# RPiHeatingArduinoOilSensorTCP.net
KiCad netlist of a schematic drawn in EAGLE
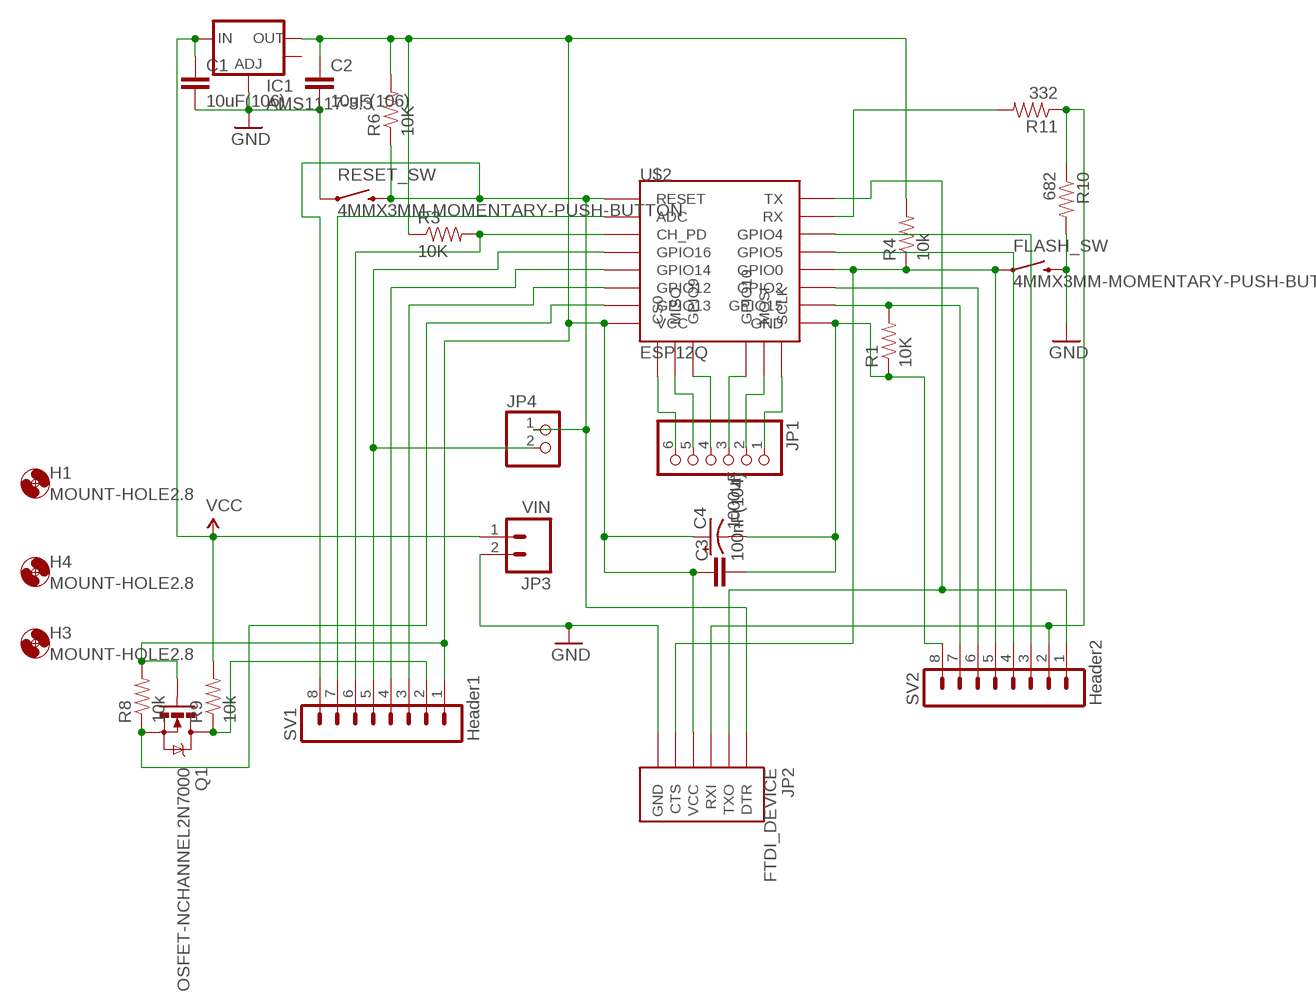
[diagram p0: schematic, sheet 1]

(export (version "E")
  (design (tool "Eeschema 10.0.6"))
  (components
    (comp (ref "C1")
      (value "10uF(106)")
      (footprint "eagle-import:0805")
      (libsource (lib "eagle-import") (part "CAP0805"))
    )
    (comp (ref "C2")
      (value "10uF(106)")
      (footprint "eagle-import:0805")
      (libsource (lib "eagle-import") (part "CAP0805"))
    )
    (comp (ref "C3")
      (value "100nF(104)")
      (footprint "eagle-import:0805")
      (libsource (lib "eagle-import") (part "CAP0805"))
    )
    (comp (ref "C4")
      (value "1000uF")
      (footprint "eagle-import:CPOL-RADIAL-1000UF-25V")
      (libsource (lib "eagle-import") (part "CAP_POLPTH4"))
    )
    (comp (ref "FLASH_SW")
      (value "4MMX3MM-MOMENTARY-PUSH-BUTTON")
      (footprint "eagle-import:4MMX3MM-MOMENTARY-PUSH-BUTTON")
      (libsource (lib "eagle-import") (part "4MMX3MM-MOMENTARY-PUSH-BUTTON"))
    )
    (comp (ref "H1")
      (value "MOUNT-HOLE2.8")
      (footprint "eagle-import:2,8")
      (libsource (lib "eagle-import") (part "MOUNT-HOLE2.8"))
    )
    (comp (ref "H3")
      (value "MOUNT-HOLE2.8")
      (footprint "eagle-import:2,8")
      (libsource (lib "eagle-import") (part "MOUNT-HOLE2.8"))
    )
    (comp (ref "H4")
      (value "MOUNT-HOLE2.8")
      (footprint "eagle-import:2,8")
      (libsource (lib "eagle-import") (part "MOUNT-HOLE2.8"))
    )
    (comp (ref "IC1")
      (value "AMS1117-3.3")
      (footprint "eagle-import:SOT223")
      (libsource (lib "eagle-import") (part "V_REG_LM1117SOT223"))
    )
    (comp (ref "JP1")
      (value "PINHD-1X6")
      (footprint "eagle-import:1X06")
      (libsource (lib "eagle-import") (part "PINHD-1X6"))
    )
    (comp (ref "JP2")
      (value "FTDI_DEVICE")
      (footprint "eagle-import:FTDI_DEVICE_SIDE")
      (libsource (lib "eagle-import") (part "FTDI_DEVICE"))
    )
    (comp (ref "JP3")
      (value "VIN")
      (footprint "eagle-import:1X02_LOCK_LONGPADS")
      (libsource (lib "eagle-import") (part "M02LOCK_LONGPADS"))
    )
    (comp (ref "JP4")
      (value "PINHD-1X2")
      (footprint "eagle-import:1X02")
      (libsource (lib "eagle-import") (part "PINHD-1X2"))
    )
    (comp (ref "Q1")
      (value "MOSFET-NCHANNEL2N7000")
      (footprint "eagle-import:TO-92")
      (libsource (lib "eagle-import") (part "MOSFET-NCHANNEL2N7000"))
    )
    (comp (ref "R1")
      (value "10K")
      (footprint "eagle-import:0805")
      (libsource (lib "eagle-import") (part "RESISTOR0805-RES"))
    )
    (comp (ref "R3")
      (value "10K")
      (footprint "eagle-import:0805")
      (libsource (lib "eagle-import") (part "RESISTOR0805-RES"))
    )
    (comp (ref "R4")
      (value "10k")
      (footprint "eagle-import:0805")
      (libsource (lib "eagle-import") (part "RESISTOR0805-RES"))
    )
    (comp (ref "R6")
      (value "10K")
      (footprint "eagle-import:0805")
      (libsource (lib "eagle-import") (part "RESISTOR0805-RES"))
    )
    (comp (ref "R8")
      (value "10k")
      (footprint "eagle-import:0805")
      (libsource (lib "eagle-import") (part "RESISTOR0805-RES"))
    )
    (comp (ref "R9")
      (value "10k")
      (footprint "eagle-import:0805")
      (libsource (lib "eagle-import") (part "RESISTOR0805-RES"))
    )
    (comp (ref "R10")
      (value "682")
      (footprint "eagle-import:0805")
      (libsource (lib "eagle-import") (part "RESISTOR0805-RES"))
    )
    (comp (ref "R11")
      (value "332")
      (footprint "eagle-import:0805")
      (libsource (lib "eagle-import") (part "RESISTOR0805-RES"))
    )
    (comp (ref "RESET_SW")
      (value "4MMX3MM-MOMENTARY-PUSH-BUTTON")
      (footprint "eagle-import:4MMX3MM-MOMENTARY-PUSH-BUTTON")
      (libsource (lib "eagle-import") (part "4MMX3MM-MOMENTARY-PUSH-BUTTON"))
    )
    (comp (ref "SV1")
      (value "Header1")
      (footprint "eagle-import:MA08-1")
      (libsource (lib "eagle-import") (part "MA08-1"))
    )
    (comp (ref "SV2")
      (value "Header2")
      (footprint "eagle-import:MA08-1")
      (libsource (lib "eagle-import") (part "MA08-1"))
    )
    (comp (ref "U$2")
      (value "ESP12Q")
      (footprint "eagle-import:ESP12Q")
      (libsource (lib "eagle-import") (part "ESP12Q"))
    )
  )
  (nets
    (net (code "1") (name "GND") (class "Default")
      (node (ref "C1") (pin "2") (pinfunction "2_2") (pintype "passive"))
      (node (ref "C2") (pin "2") (pinfunction "2_2") (pintype "passive"))
      (node (ref "FLASH_SW") (pin "P$2") (pinfunction "2_P$2") (pintype "passive"))
      (node (ref "IC1") (pin "1") (pinfunction "ADJ_1") (pintype "input"))
      (node (ref "JP2") (pin "P$6") (pinfunction "GND_P$6") (pintype "bidirectional"))
      (node (ref "JP3") (pin "2") (pinfunction "2_2") (pintype "passive"))
      (node (ref "R10") (pin "2") (pinfunction "2_2") (pintype "passive"))
      (node (ref "RESET_SW") (pin "P$1") (pinfunction "1_P$1") (pintype "passive"))
    )
    (net (code "2") (name "Net-(C4-+)") (class "Default")
      (node (ref "C2") (pin "1") (pinfunction "1_1") (pintype "passive"))
      (node (ref "C3") (pin "1") (pinfunction "1_1") (pintype "passive"))
      (node (ref "C4") (pin "1") (pinfunction "+_1") (pintype "passive"))
      (node (ref "IC1") (pin "2") (pinfunction "OUT_2") (pintype "output"))
      (node (ref "JP2") (pin "P$4") (pinfunction "VCC_P$4") (pintype "bidirectional"))
      (node (ref "Q1") (pin "2") (pinfunction "G_2") (pintype "passive"))
      (node (ref "R3") (pin "1") (pinfunction "1_1") (pintype "passive"))
      (node (ref "R4") (pin "2") (pinfunction "2_2") (pintype "passive"))
      (node (ref "R6") (pin "2") (pinfunction "2_2") (pintype "passive"))
      (node (ref "R8") (pin "2") (pinfunction "2_2") (pintype "passive"))
      (node (ref "SV1") (pin "1") (pinfunction "1_1") (pintype "passive"))
      (node (ref "U$2") (pin "VCC") (pinfunction "VCC_VCC") (pintype "bidirectional"))
    )
    (net (code "3") (name "Net-(C4--)") (class "Default")
      (node (ref "C3") (pin "2") (pinfunction "2_2") (pintype "passive"))
      (node (ref "C4") (pin "2") (pinfunction "-_2") (pintype "passive"))
      (node (ref "R1") (pin "1") (pinfunction "1_1") (pintype "passive"))
      (node (ref "SV2") (pin "8") (pinfunction "8_8") (pintype "passive"))
      (node (ref "U$2") (pin "GND") (pinfunction "GND_GND") (pintype "bidirectional"))
    )
    (net (code "4") (name "Net-(FLASH_SW-1)") (class "Default")
      (node (ref "FLASH_SW") (pin "P$1") (pinfunction "1_P$1") (pintype "passive"))
      (node (ref "JP2") (pin "P$5") (pinfunction "CTS_P$5") (pintype "bidirectional"))
      (node (ref "R4") (pin "1") (pinfunction "1_1") (pintype "passive"))
      (node (ref "SV2") (pin "5") (pinfunction "5_5") (pintype "passive"))
      (node (ref "U$2") (pin "GPIO0") (pinfunction "GPIO0_GPIO0") (pintype "bidirectional"))
    )
    (net (code "5") (name "Net-(JP1-Pad1)") (class "Default")
      (node (ref "JP1") (pin "1") (pinfunction "1_1") (pintype "passive"))
      (node (ref "U$2") (pin "SCLK") (pinfunction "SCLK_SCLK") (pintype "bidirectional"))
    )
    (net (code "6") (name "Net-(JP1-Pad2)") (class "Default")
      (node (ref "JP1") (pin "2") (pinfunction "2_2") (pintype "passive"))
      (node (ref "U$2") (pin "MOSI") (pinfunction "MOSI_MOSI") (pintype "bidirectional"))
    )
    (net (code "7") (name "Net-(JP1-Pad3)") (class "Default")
      (node (ref "JP1") (pin "3") (pinfunction "3_3") (pintype "passive"))
      (node (ref "U$2") (pin "GPIO10") (pinfunction "GPIO10_GPIO10") (pintype "bidirectional"))
    )
    (net (code "8") (name "Net-(JP1-Pad4)") (class "Default")
      (node (ref "JP1") (pin "4") (pinfunction "4_4") (pintype "passive"))
      (node (ref "U$2") (pin "GPIO9") (pinfunction "GPIO9_GPIO9") (pintype "bidirectional"))
    )
    (net (code "9") (name "Net-(JP1-Pad5)") (class "Default")
      (node (ref "JP1") (pin "5") (pinfunction "5_5") (pintype "passive"))
      (node (ref "U$2") (pin "MISO") (pinfunction "MISO_MISO") (pintype "bidirectional"))
    )
    (net (code "10") (name "Net-(JP1-Pad6)") (class "Default")
      (node (ref "JP1") (pin "6") (pinfunction "6_6") (pintype "passive"))
      (node (ref "U$2") (pin "CS0") (pinfunction "CS0_CS0") (pintype "bidirectional"))
    )
    (net (code "11") (name "Net-(JP2-DTR)") (class "Default")
      (node (ref "JP2") (pin "P$1") (pinfunction "DTR_P$1") (pintype "bidirectional"))
      (node (ref "JP4") (pin "1") (pinfunction "1_1") (pintype "passive"))
      (node (ref "R6") (pin "1") (pinfunction "1_1") (pintype "passive"))
      (node (ref "RESET_SW") (pin "P$2") (pinfunction "2_P$2") (pintype "passive"))
      (node (ref "SV1") (pin "8") (pinfunction "8_8") (pintype "passive"))
      (node (ref "U$2") (pin "RESET") (pinfunction "RESET_RESET") (pintype "bidirectional"))
    )
    (net (code "12") (name "Net-(JP2-RXI)") (class "Default")
      (node (ref "JP2") (pin "P$3") (pinfunction "RXI_P$3") (pintype "bidirectional"))
      (node (ref "R10") (pin "1") (pinfunction "1_1") (pintype "passive"))
      (node (ref "R11") (pin "1") (pinfunction "1_1") (pintype "passive"))
      (node (ref "SV2") (pin "2") (pinfunction "2_2") (pintype "passive"))
    )
    (net (code "13") (name "Net-(JP2-TXO)") (class "Default")
      (node (ref "JP2") (pin "P$2") (pinfunction "TXO_P$2") (pintype "bidirectional"))
      (node (ref "SV2") (pin "1") (pinfunction "1_1") (pintype "passive"))
      (node (ref "U$2") (pin "TX") (pinfunction "TX_TX") (pintype "bidirectional"))
    )
    (net (code "14") (name "Net-(JP4-Pad2)") (class "Default")
      (node (ref "JP4") (pin "2") (pinfunction "2_2") (pintype "passive"))
      (node (ref "SV1") (pin "5") (pinfunction "5_5") (pintype "passive"))
      (node (ref "U$2") (pin "GPIO16") (pinfunction "GPIO16_GPIO16") (pintype "bidirectional"))
    )
    (net (code "15") (name "Net-(Q1-D)") (class "Default")
      (node (ref "Q1") (pin "3") (pinfunction "D_3") (pintype "passive"))
      (node (ref "R9") (pin "1") (pinfunction "1_1") (pintype "passive"))
      (node (ref "SV1") (pin "2") (pinfunction "2_2") (pintype "passive"))
    )
    (net (code "16") (name "Net-(Q1-S)") (class "Default")
      (node (ref "Q1") (pin "1") (pinfunction "S_1") (pintype "passive"))
      (node (ref "R8") (pin "1") (pinfunction "1_1") (pintype "passive"))
      (node (ref "U$2") (pin "GPIO13") (pinfunction "GPIO13_GPIO13") (pintype "bidirectional"))
    )
    (net (code "17") (name "Net-(R1-Pad2)") (class "Default")
      (node (ref "R1") (pin "2") (pinfunction "2_2") (pintype "passive"))
      (node (ref "SV2") (pin "7") (pinfunction "7_7") (pintype "passive"))
      (node (ref "U$2") (pin "GPIO15") (pinfunction "GPIO15_GPIO15") (pintype "bidirectional"))
    )
    (net (code "18") (name "Net-(R3-Pad2)") (class "Default")
      (node (ref "R3") (pin "2") (pinfunction "2_2") (pintype "passive"))
      (node (ref "SV1") (pin "6") (pinfunction "6_6") (pintype "passive"))
      (node (ref "U$2") (pin "CH_PD") (pinfunction "CH_PD_CH_PD") (pintype "bidirectional"))
    )
    (net (code "19") (name "Net-(R11-Pad2)") (class "Default")
      (node (ref "R11") (pin "2") (pinfunction "2_2") (pintype "passive"))
      (node (ref "U$2") (pin "RX") (pinfunction "RX_RX") (pintype "bidirectional"))
    )
    (net (code "20") (name "Net-(SV1-Pad3)") (class "Default")
      (node (ref "SV1") (pin "3") (pinfunction "3_3") (pintype "passive"))
      (node (ref "U$2") (pin "GPIO12") (pinfunction "GPIO12_GPIO12") (pintype "bidirectional"))
    )
    (net (code "21") (name "Net-(SV1-Pad4)") (class "Default")
      (node (ref "SV1") (pin "4") (pinfunction "4_4") (pintype "passive"))
      (node (ref "U$2") (pin "GPIO14") (pinfunction "GPIO14_GPIO14") (pintype "bidirectional"))
    )
    (net (code "22") (name "Net-(SV1-Pad7)") (class "Default")
      (node (ref "SV1") (pin "7") (pinfunction "7_7") (pintype "passive"))
      (node (ref "U$2") (pin "ADC") (pinfunction "ADC_ADC") (pintype "bidirectional"))
    )
    (net (code "23") (name "Net-(SV2-Pad3)") (class "Default")
      (node (ref "SV2") (pin "3") (pinfunction "3_3") (pintype "passive"))
      (node (ref "U$2") (pin "GPIO4") (pinfunction "GPIO4_GPIO4") (pintype "bidirectional"))
    )
    (net (code "24") (name "Net-(SV2-Pad4)") (class "Default")
      (node (ref "SV2") (pin "4") (pinfunction "4_4") (pintype "passive"))
      (node (ref "U$2") (pin "GPIO5") (pinfunction "GPIO5_GPIO5") (pintype "bidirectional"))
    )
    (net (code "25") (name "Net-(SV2-Pad6)") (class "Default")
      (node (ref "SV2") (pin "6") (pinfunction "6_6") (pintype "passive"))
      (node (ref "U$2") (pin "GPIO2") (pinfunction "GPIO2_GPIO2") (pintype "bidirectional"))
    )
    (net (code "26") (name "VCC") (class "Default")
      (node (ref "C1") (pin "1") (pinfunction "1_1") (pintype "passive"))
      (node (ref "IC1") (pin "3") (pinfunction "IN_3") (pintype "input"))
      (node (ref "JP3") (pin "1") (pinfunction "1_1") (pintype "passive"))
      (node (ref "R9") (pin "2") (pinfunction "2_2") (pintype "passive"))
    )
    (net (code "27") (name "unconnected-(IC1-OUT-Pad4)") (class "Default")
      (node (ref "IC1") (pin "4") (pinfunction "OUT_4") (pintype "output"))
    )
  )
)
